# 05_LMS7002M_RF.net
KiCad netlist of a schematic drawn in Altium Designer
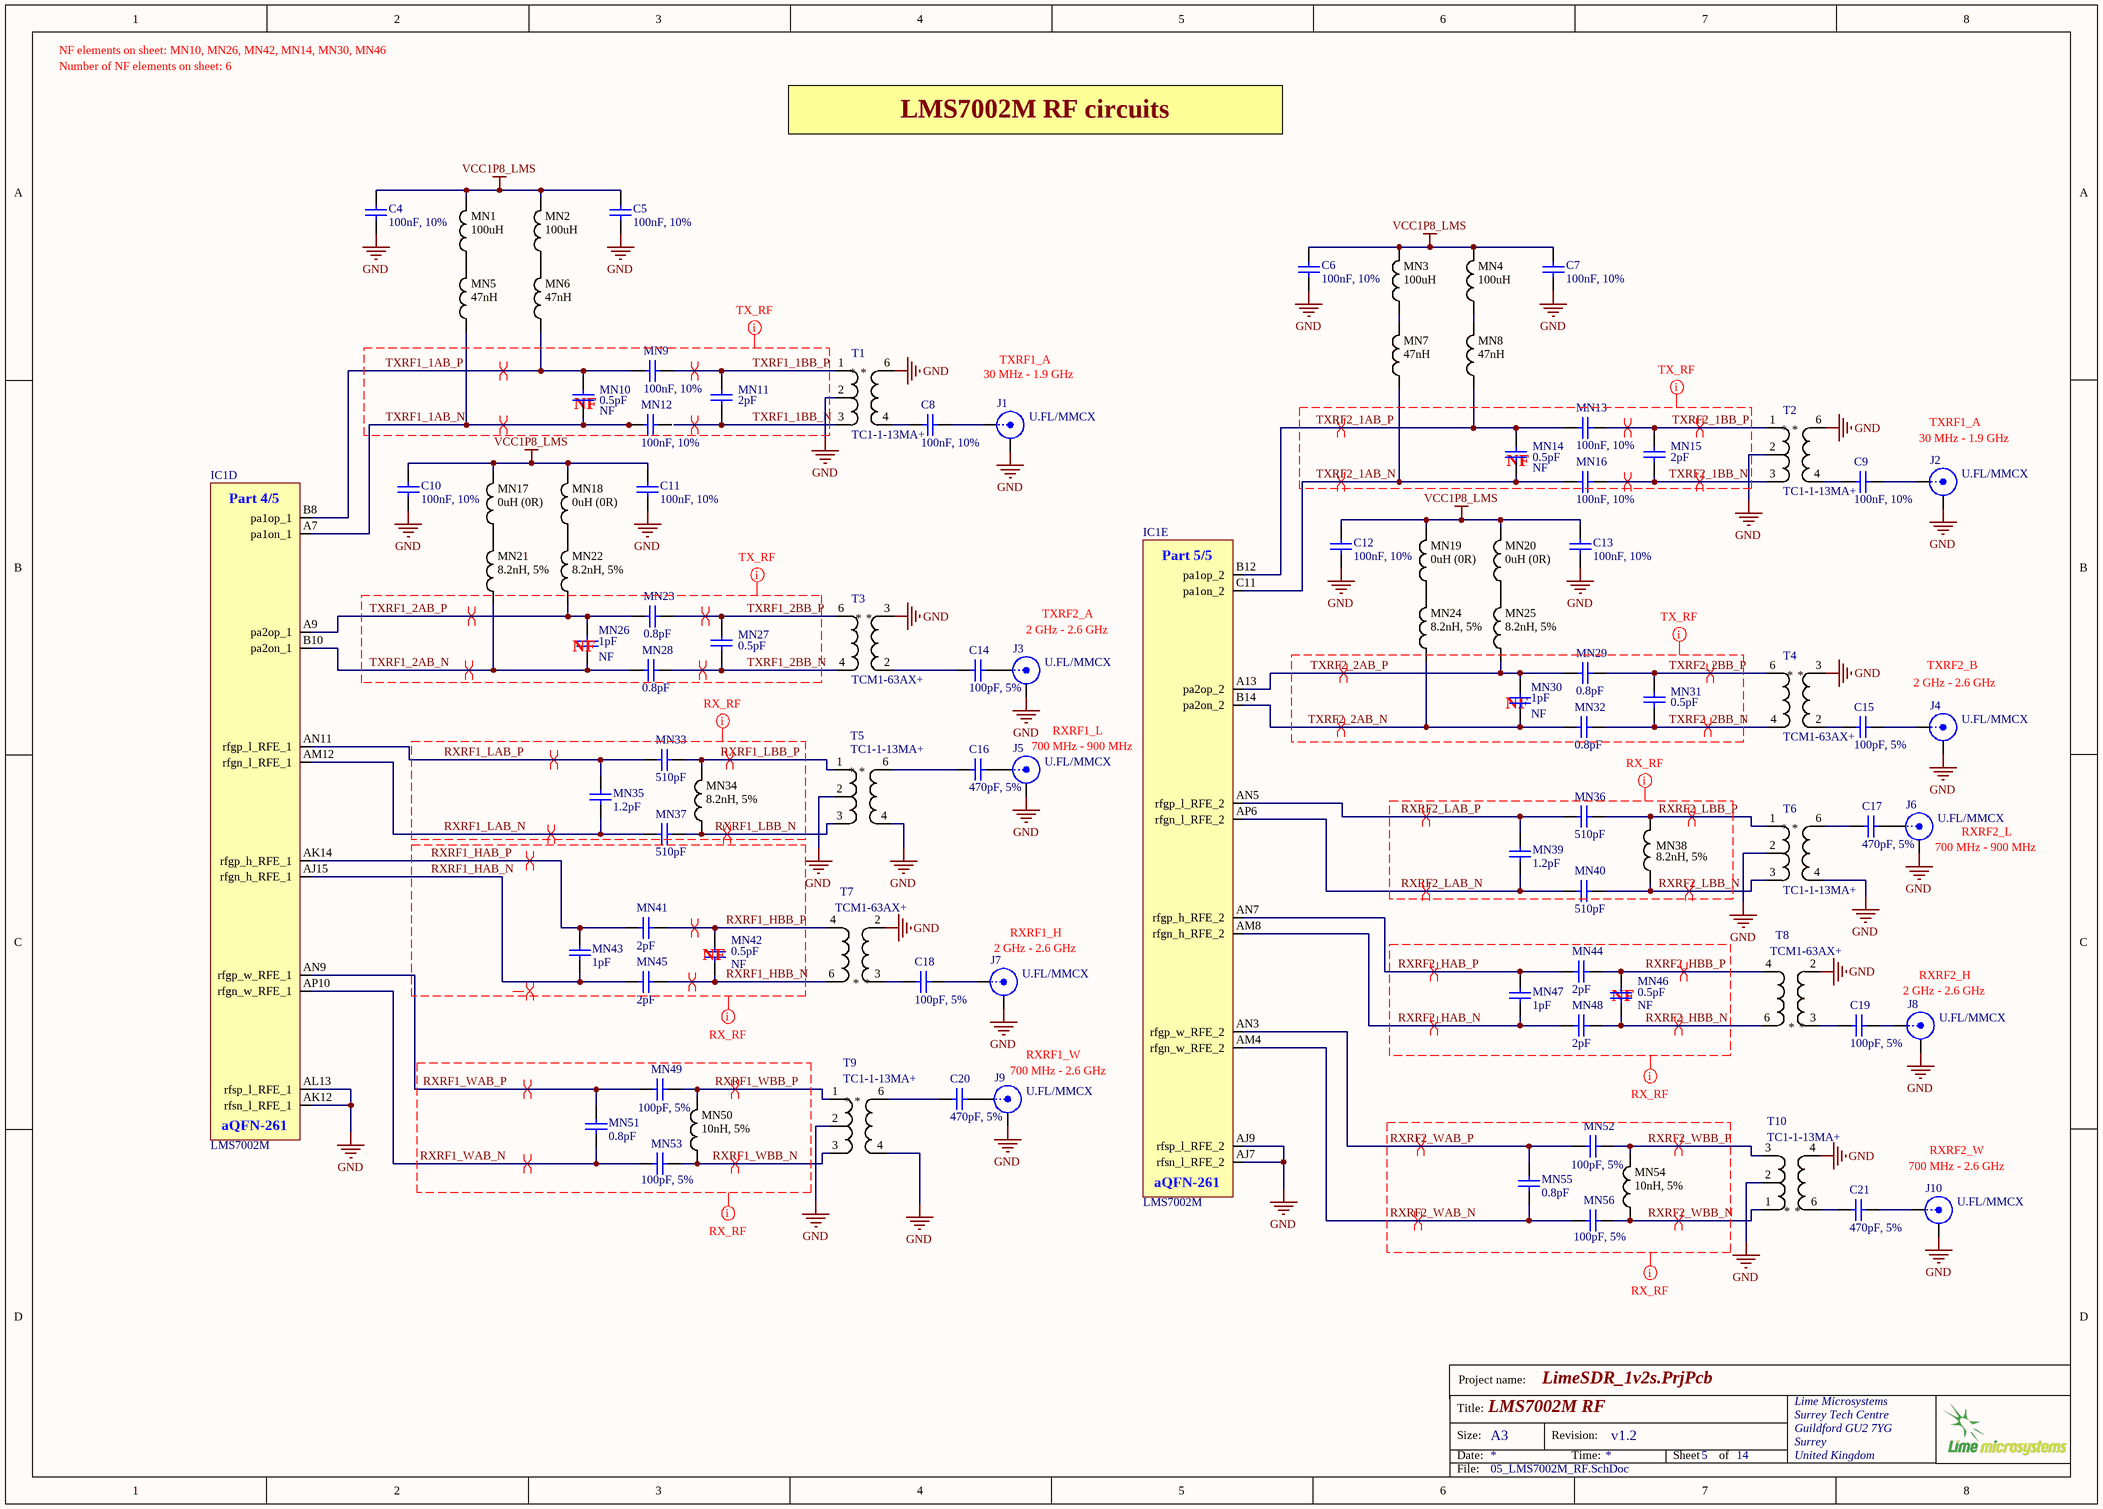
[diagram p0: 05_LMS7002M_RF.SchDoc]

(export (version "E")
  (design (tool "Eeschema 10.0.6"))
  (components
    (comp (ref "C4")
      (value "100nF, 10%")
      (footprint "CAP0402")
      (fields
        (field (name "MANUFACTURER") "Murata Electronics")
        (field (name "TOLERANCE") "10 %")
        (field (name "MANUFACTURER PART NUMBER") "GRM155R71C104KA88D")
      )
      (libsource (lib "LimeMicroAltiumLib_schLib") (part "Cap_0402"))
    )
    (comp (ref "C5")
      (value "100nF, 10%")
      (footprint "CAP0402")
      (fields
        (field (name "MANUFACTURER") "Murata Electronics")
        (field (name "TOLERANCE") "10 %")
        (field (name "MANUFACTURER PART NUMBER") "GRM155R71C104KA88D")
      )
      (libsource (lib "LimeMicroAltiumLib_schLib") (part "Cap_0402"))
    )
    (comp (ref "C6")
      (value "100nF, 10%")
      (footprint "CAP0402")
      (fields
        (field (name "MANUFACTURER") "Murata Electronics")
        (field (name "TOLERANCE") "10 %")
        (field (name "MANUFACTURER PART NUMBER") "GRM155R71C104KA88D")
      )
      (libsource (lib "LimeMicroAltiumLib_schLib") (part "Cap_0402"))
    )
    (comp (ref "C7")
      (value "100nF, 10%")
      (footprint "CAP0402")
      (fields
        (field (name "MANUFACTURER") "Murata Electronics")
        (field (name "TOLERANCE") "10 %")
        (field (name "MANUFACTURER PART NUMBER") "GRM155R71C104KA88D")
      )
      (libsource (lib "LimeMicroAltiumLib_schLib") (part "Cap_0402"))
    )
    (comp (ref "C8")
      (value "100nF, 10%")
      (footprint "CAP0402")
      (fields
        (field (name "MANUFACTURER") "Murata Electronics")
        (field (name "TOLERANCE") "10 %")
        (field (name "MANUFACTURER PART NUMBER") "GRM155R71C104KA88D")
      )
      (libsource (lib "LimeMicroAltiumLib_schLib") (part "Cap_0402"))
    )
    (comp (ref "C9")
      (value "100nF, 10%")
      (footprint "CAP0402")
      (fields
        (field (name "MANUFACTURER") "Murata Electronics")
        (field (name "TOLERANCE") "10 %")
        (field (name "MANUFACTURER PART NUMBER") "GRM155R71C104KA88D")
      )
      (libsource (lib "LimeMicroAltiumLib_schLib") (part "Cap_0402"))
    )
    (comp (ref "C10")
      (value "100nF, 10%")
      (footprint "CAP0402")
      (fields
        (field (name "MANUFACTURER") "Murata Electronics")
        (field (name "TOLERANCE") "10 %")
        (field (name "MANUFACTURER PART NUMBER") "GRM155R71C104KA88D")
      )
      (libsource (lib "LimeMicroAltiumLib_schLib") (part "Cap_0402"))
    )
    (comp (ref "C11")
      (value "100nF, 10%")
      (footprint "CAP0402")
      (fields
        (field (name "MANUFACTURER") "Murata Electronics")
        (field (name "TOLERANCE") "10 %")
        (field (name "MANUFACTURER PART NUMBER") "GRM155R71C104KA88D")
      )
      (libsource (lib "LimeMicroAltiumLib_schLib") (part "Cap_0402"))
    )
    (comp (ref "C12")
      (value "100nF, 10%")
      (footprint "CAP0402")
      (fields
        (field (name "MANUFACTURER") "Murata Electronics")
        (field (name "TOLERANCE") "10 %")
        (field (name "MANUFACTURER PART NUMBER") "GRM155R71C104KA88D")
      )
      (libsource (lib "LimeMicroAltiumLib_schLib") (part "Cap_0402"))
    )
    (comp (ref "C13")
      (value "100nF, 10%")
      (footprint "CAP0402")
      (fields
        (field (name "MANUFACTURER") "Murata Electronics")
        (field (name "TOLERANCE") "10 %")
        (field (name "MANUFACTURER PART NUMBER") "GRM155R71C104KA88D")
      )
      (libsource (lib "LimeMicroAltiumLib_schLib") (part "Cap_0402"))
    )
    (comp (ref "C14")
      (value "100pF, 5%")
      (footprint "CAP0402")
      (fields (field (name "TOLERANCE") "±5%") (field (name "MANUFACTURER") "Yageo"))
      (libsource (lib "LimeMicroAltiumLib_schLib") (part "Cap_0402"))
    )
    (comp (ref "C15")
      (value "100pF, 5%")
      (footprint "CAP0402")
      (fields (field (name "TOLERANCE") "±5%") (field (name "MANUFACTURER") "Yageo"))
      (libsource (lib "LimeMicroAltiumLib_schLib") (part "Cap_0402"))
    )
    (comp (ref "C16")
      (value "470pF, 5%")
      (footprint "CAP0402")
      (fields
        (field (name "MANUFACTURER PART NUMBER") "C1005C0G1H471J050BA")
        (field (name "TOLERANCE") "±5%")
        (field (name "MANUFACTURER") "TDK Corporation")
      )
      (libsource (lib "LimeMicroAltiumLib_schLib") (part "Cap_0402"))
    )
    (comp (ref "C17")
      (value "470pF, 5%")
      (footprint "CAP0402")
      (fields
        (field (name "MANUFACTURER PART NUMBER") "C1005C0G1H471J050BA")
        (field (name "TOLERANCE") "±5%")
        (field (name "MANUFACTURER") "TDK Corporation")
      )
      (libsource (lib "LimeMicroAltiumLib_schLib") (part "Cap_0402"))
    )
    (comp (ref "C18")
      (value "100pF, 5%")
      (footprint "CAP0402")
      (fields (field (name "TOLERANCE") "±5%") (field (name "MANUFACTURER") "Yageo"))
      (libsource (lib "LimeMicroAltiumLib_schLib") (part "Cap_0402"))
    )
    (comp (ref "C19")
      (value "100pF, 5%")
      (footprint "CAP0402")
      (fields (field (name "TOLERANCE") "±5%") (field (name "MANUFACTURER") "Yageo"))
      (libsource (lib "LimeMicroAltiumLib_schLib") (part "Cap_0402"))
    )
    (comp (ref "C20")
      (value "470pF, 5%")
      (footprint "CAP0402")
      (fields
        (field (name "MANUFACTURER PART NUMBER") "C1005C0G1H471J050BA")
        (field (name "TOLERANCE") "±5%")
        (field (name "MANUFACTURER") "TDK Corporation")
      )
      (libsource (lib "LimeMicroAltiumLib_schLib") (part "Cap_0402"))
    )
    (comp (ref "C21")
      (value "470pF, 5%")
      (footprint "CAP0402")
      (fields
        (field (name "MANUFACTURER PART NUMBER") "C1005C0G1H471J050BA")
        (field (name "TOLERANCE") "±5%")
        (field (name "MANUFACTURER") "TDK Corporation")
      )
      (libsource (lib "LimeMicroAltiumLib_schLib") (part "Cap_0402"))
    )
    (comp (ref "IC1")
      (value "LMS7002M")
      (footprint "LMS7002M")
      (fields (field (name "MANUFACTURER") "Lime Microsystems"))
      (libsource (lib "LimeMicroAltiumLib_schLib") (part "LMS7002M"))
    )
    (comp (ref "J1")
      (value "U.FL/MMCX")
      (footprint "MMCX_UFL_conn_u")
      (description "CONN UMC RCPT STR 50 OHM SMD")
      (fields (field (name "MANUFACTURER") "Molex, LLC"))
      (libsource (lib "LimeMicroAltiumLib_schLib") (part "RF_IF_connector"))
    )
    (comp (ref "J2")
      (value "U.FL/MMCX")
      (footprint "MMCX_UFL_conn_u")
      (description "CONN UMC RCPT STR 50 OHM SMD")
      (fields (field (name "MANUFACTURER") "Molex, LLC"))
      (libsource (lib "LimeMicroAltiumLib_schLib") (part "RF_IF_connector"))
    )
    (comp (ref "J3")
      (value "U.FL/MMCX")
      (footprint "MMCX_UFL_conn_u")
      (description "CONN UMC RCPT STR 50 OHM SMD")
      (fields (field (name "MANUFACTURER") "Molex, LLC"))
      (libsource (lib "LimeMicroAltiumLib_schLib") (part "RF_IF_connector"))
    )
    (comp (ref "J4")
      (value "U.FL/MMCX")
      (footprint "MMCX_UFL_conn_u")
      (description "CONN UMC RCPT STR 50 OHM SMD")
      (fields (field (name "MANUFACTURER") "Molex, LLC"))
      (libsource (lib "LimeMicroAltiumLib_schLib") (part "RF_IF_connector"))
    )
    (comp (ref "J5")
      (value "U.FL/MMCX")
      (footprint "MMCX_UFL_conn_u")
      (description "CONN UMC RCPT STR 50 OHM SMD")
      (fields (field (name "MANUFACTURER") "Molex, LLC"))
      (libsource (lib "LimeMicroAltiumLib_schLib") (part "RF_IF_connector"))
    )
    (comp (ref "J6")
      (value "U.FL/MMCX")
      (footprint "MMCX_UFL_conn_u")
      (description "CONN UMC RCPT STR 50 OHM SMD")
      (fields (field (name "MANUFACTURER") "Molex, LLC"))
      (libsource (lib "LimeMicroAltiumLib_schLib") (part "RF_IF_connector"))
    )
    (comp (ref "J7")
      (value "U.FL/MMCX")
      (footprint "MMCX_UFL_conn_u")
      (description "CONN UMC RCPT STR 50 OHM SMD")
      (fields (field (name "MANUFACTURER") "Molex, LLC"))
      (libsource (lib "LimeMicroAltiumLib_schLib") (part "RF_IF_connector"))
    )
    (comp (ref "J8")
      (value "U.FL/MMCX")
      (footprint "MMCX_UFL_conn_u")
      (description "CONN UMC RCPT STR 50 OHM SMD")
      (fields (field (name "MANUFACTURER") "Molex, LLC"))
      (libsource (lib "LimeMicroAltiumLib_schLib") (part "RF_IF_connector"))
    )
    (comp (ref "J9")
      (value "U.FL/MMCX")
      (footprint "MMCX_UFL_conn_u")
      (description "CONN UMC RCPT STR 50 OHM SMD")
      (fields (field (name "MANUFACTURER") "Molex, LLC"))
      (libsource (lib "LimeMicroAltiumLib_schLib") (part "RF_IF_connector"))
    )
    (comp (ref "J10")
      (value "U.FL/MMCX")
      (footprint "MMCX_UFL_conn_u")
      (description "CONN UMC RCPT STR 50 OHM SMD")
      (fields (field (name "MANUFACTURER") "Molex, LLC"))
      (libsource (lib "LimeMicroAltiumLib_schLib") (part "RF_IF_connector"))
    )
    (comp (ref "MN1")
      (value "100uH")
      (footprint "RES0805")
      (fields
        (field (name "TOLERANCE") "±10%")
        (field (name "MANUFACTURER") "TDK Corporation")
        (field (name "MANUFACTURER PART NUMBER") "MLF2012C101KT000")
      )
      (libsource (lib "LimeMicroAltiumLib_schLib") (part "Inductor_0603"))
    )
    (comp (ref "MN2")
      (value "100uH")
      (footprint "RES0805")
      (fields
        (field (name "TOLERANCE") "±10%")
        (field (name "MANUFACTURER") "TDK Corporation")
        (field (name "MANUFACTURER PART NUMBER") "MLF2012C101KT000")
      )
      (libsource (lib "LimeMicroAltiumLib_schLib") (part "Inductor_0603"))
    )
    (comp (ref "MN3")
      (value "100uH")
      (footprint "RES0805")
      (fields
        (field (name "TOLERANCE") "±10%")
        (field (name "MANUFACTURER") "TDK Corporation")
        (field (name "MANUFACTURER PART NUMBER") "MLF2012C101KT000")
      )
      (libsource (lib "LimeMicroAltiumLib_schLib") (part "Inductor_0603"))
    )
    (comp (ref "MN4")
      (value "100uH")
      (footprint "RES0805")
      (fields
        (field (name "TOLERANCE") "±10%")
        (field (name "MANUFACTURER") "TDK Corporation")
        (field (name "MANUFACTURER PART NUMBER") "MLF2012C101KT000")
      )
      (libsource (lib "LimeMicroAltiumLib_schLib") (part "Inductor_0603"))
    )
    (comp (ref "MN5")
      (value "47nH")
      (footprint "RES0402")
      (fields
        (field (name "MANUFACTURER") "COILCRAFT")
        (field (name "MANUFACTURER PART NUMBER") "0402HP-47NXJLU")
      )
      (libsource (lib "LimeMicroAltiumLib_schLib") (part "Inductor_0603"))
    )
    (comp (ref "MN6")
      (value "47nH")
      (footprint "RES0402")
      (fields
        (field (name "MANUFACTURER") "COILCRAFT")
        (field (name "MANUFACTURER PART NUMBER") "0402HP-47NXJLU")
      )
      (libsource (lib "LimeMicroAltiumLib_schLib") (part "Inductor_0603"))
    )
    (comp (ref "MN7")
      (value "47nH")
      (footprint "RES0402")
      (fields
        (field (name "MANUFACTURER") "COILCRAFT")
        (field (name "MANUFACTURER PART NUMBER") "0402HP-47NXJLU")
      )
      (libsource (lib "LimeMicroAltiumLib_schLib") (part "Inductor_0603"))
    )
    (comp (ref "MN8")
      (value "47nH")
      (footprint "RES0402")
      (fields
        (field (name "MANUFACTURER") "COILCRAFT")
        (field (name "MANUFACTURER PART NUMBER") "0402HP-47NXJLU")
      )
      (libsource (lib "LimeMicroAltiumLib_schLib") (part "Inductor_0603"))
    )
    (comp (ref "MN9")
      (value "100nF, 10%")
      (footprint "CAP0402")
      (fields
        (field (name "MANUFACTURER") "Murata Electronics")
        (field (name "TOLERANCE") "10 %")
        (field (name "MANUFACTURER PART NUMBER") "GRM155R71C104KA88D")
      )
      (libsource (lib "LimeMicroAltiumLib_schLib") (part "Cap_0402"))
    )
    (comp (ref "MN10")
      (value "0.5pF")
      (footprint "CAP0402")
      (fields
        (field (name "ASSEMBLY INFO") "NF")
        (field (name "TOLERANCE") "±0.25pF")
        (field (name "MANUFACTURER") "Yageo")
      )
      (libsource (lib "LimeMicroAltiumLib_schLib") (part "Cap_0402"))
    )
    (comp (ref "MN11")
      (value "2pF")
      (footprint "CAP0402")
      (fields (field (name "MANUFACTURER PART NUMBER") "04025U2R0BAT2A") (field (name "MANUFACTURER") "AVX"))
      (libsource (lib "LimeMicroAltiumLib_schLib") (part "Cap_0402"))
    )
    (comp (ref "MN12")
      (value "100nF, 10%")
      (footprint "CAP0402")
      (fields
        (field (name "MANUFACTURER") "Murata Electronics")
        (field (name "TOLERANCE") "10 %")
        (field (name "MANUFACTURER PART NUMBER") "GRM155R71C104KA88D")
      )
      (libsource (lib "LimeMicroAltiumLib_schLib") (part "Cap_0402"))
    )
    (comp (ref "MN13")
      (value "100nF, 10%")
      (footprint "CAP0402")
      (fields
        (field (name "MANUFACTURER") "Murata Electronics")
        (field (name "TOLERANCE") "10 %")
        (field (name "MANUFACTURER PART NUMBER") "GRM155R71C104KA88D")
      )
      (libsource (lib "LimeMicroAltiumLib_schLib") (part "Cap_0402"))
    )
    (comp (ref "MN14")
      (value "0.5pF")
      (footprint "CAP0402")
      (fields
        (field (name "ASSEMBLY INFO") "NF")
        (field (name "TOLERANCE") "±0.25pF")
        (field (name "MANUFACTURER") "Yageo")
      )
      (libsource (lib "LimeMicroAltiumLib_schLib") (part "Cap_0402"))
    )
    (comp (ref "MN15")
      (value "2pF")
      (footprint "CAP0402")
      (fields (field (name "MANUFACTURER PART NUMBER") "04025U2R0BAT2A") (field (name "MANUFACTURER") "AVX"))
      (libsource (lib "LimeMicroAltiumLib_schLib") (part "Cap_0402"))
    )
    (comp (ref "MN16")
      (value "100nF, 10%")
      (footprint "CAP0402")
      (fields
        (field (name "MANUFACTURER") "Murata Electronics")
        (field (name "TOLERANCE") "10 %")
        (field (name "MANUFACTURER PART NUMBER") "GRM155R71C104KA88D")
      )
      (libsource (lib "LimeMicroAltiumLib_schLib") (part "Cap_0402"))
    )
    (comp (ref "MN17")
      (value "0uH (0R)")
      (footprint "RES0805")
      (fields (field (name "MANUFACTURER") "BOURNS"))
      (libsource (lib "LimeMicroAltiumLib_schLib") (part "Inductor_0603"))
    )
    (comp (ref "MN18")
      (value "0uH (0R)")
      (footprint "RES0805")
      (fields (field (name "MANUFACTURER") "BOURNS"))
      (libsource (lib "LimeMicroAltiumLib_schLib") (part "Inductor_0603"))
    )
    (comp (ref "MN19")
      (value "0uH (0R)")
      (footprint "RES0805")
      (fields (field (name "MANUFACTURER") "BOURNS"))
      (libsource (lib "LimeMicroAltiumLib_schLib") (part "Inductor_0603"))
    )
    (comp (ref "MN20")
      (value "0uH (0R)")
      (footprint "RES0805")
      (fields (field (name "MANUFACTURER") "BOURNS"))
      (libsource (lib "LimeMicroAltiumLib_schLib") (part "Inductor_0603"))
    )
    (comp (ref "MN21")
      (value "8.2nH, 5%")
      (footprint "RES0402")
      (fields (field (name "MANUFACTURER") "COILCRAFT"))
      (libsource (lib "LimeMicroAltiumLib_schLib") (part "Inductor_0603"))
    )
    (comp (ref "MN22")
      (value "8.2nH, 5%")
      (footprint "RES0402")
      (fields (field (name "MANUFACTURER") "COILCRAFT"))
      (libsource (lib "LimeMicroAltiumLib_schLib") (part "Inductor_0603"))
    )
    (comp (ref "MN23")
      (value "0.8pF")
      (footprint "CAP0402")
      (fields
        (field (name "TOLERANCE") "±0.1pF")
        (field (name "MANUFACTURER") "Murata Electronics North America")
        (field (name "MANUFACTURER PART NUMBER") "GRM1555C1HR80BA01D")
      )
      (libsource (lib "LimeMicroAltiumLib_schLib") (part "Cap_0402"))
    )
    (comp (ref "MN24")
      (value "8.2nH, 5%")
      (footprint "RES0402")
      (fields (field (name "MANUFACTURER") "COILCRAFT"))
      (libsource (lib "LimeMicroAltiumLib_schLib") (part "Inductor_0603"))
    )
    (comp (ref "MN25")
      (value "8.2nH, 5%")
      (footprint "RES0402")
      (fields (field (name "MANUFACTURER") "COILCRAFT"))
      (libsource (lib "LimeMicroAltiumLib_schLib") (part "Inductor_0603"))
    )
    (comp (ref "MN26")
      (value "1pF")
      (footprint "CAP0402")
      (fields
        (field (name "ASSEMBLY INFO") "NF")
        (field (name "MANUFACTURER") "TDK Corporation")
        (field (name "TOLERANCE") "±0.1pF")
      )
      (libsource (lib "LimeMicroAltiumLib_schLib") (part "Cap_0402"))
    )
    (comp (ref "MN27")
      (value "0.5pF")
      (footprint "CAP0402")
      (fields (field (name "TOLERANCE") "±0.25pF") (field (name "MANUFACTURER") "Yageo"))
      (libsource (lib "LimeMicroAltiumLib_schLib") (part "Cap_0402"))
    )
    (comp (ref "MN28")
      (value "0.8pF")
      (footprint "CAP0402")
      (fields
        (field (name "TOLERANCE") "±0.1pF")
        (field (name "MANUFACTURER") "Murata Electronics North America")
        (field (name "MANUFACTURER PART NUMBER") "GRM1555C1HR80BA01D")
      )
      (libsource (lib "LimeMicroAltiumLib_schLib") (part "Cap_0402"))
    )
    (comp (ref "MN29")
      (value "0.8pF")
      (footprint "CAP0402")
      (fields
        (field (name "TOLERANCE") "±0.1pF")
        (field (name "MANUFACTURER") "Murata Electronics North America")
        (field (name "MANUFACTURER PART NUMBER") "GRM1555C1HR80BA01D")
      )
      (libsource (lib "LimeMicroAltiumLib_schLib") (part "Cap_0402"))
    )
    (comp (ref "MN30")
      (value "1pF")
      (footprint "CAP0402")
      (fields
        (field (name "ASSEMBLY INFO") "NF")
        (field (name "MANUFACTURER") "TDK Corporation")
        (field (name "TOLERANCE") "±0.1pF")
      )
      (libsource (lib "LimeMicroAltiumLib_schLib") (part "Cap_0402"))
    )
    (comp (ref "MN31")
      (value "0.5pF")
      (footprint "CAP0402")
      (fields (field (name "TOLERANCE") "±0.25pF") (field (name "MANUFACTURER") "Yageo"))
      (libsource (lib "LimeMicroAltiumLib_schLib") (part "Cap_0402"))
    )
    (comp (ref "MN32")
      (value "0.8pF")
      (footprint "CAP0402")
      (fields
        (field (name "TOLERANCE") "±0.1pF")
        (field (name "MANUFACTURER") "Murata Electronics North America")
        (field (name "MANUFACTURER PART NUMBER") "GRM1555C1HR80BA01D")
      )
      (libsource (lib "LimeMicroAltiumLib_schLib") (part "Cap_0402"))
    )
    (comp (ref "MN33")
      (value "510pF")
      (footprint "CAP0402")
      (fields
        (field (name "TOLERANCE") "±5%")
        (field (name "MANUFACTURER") "Murata Electronics North America")
        (field (name "MANUFACTURER PART NUMBER") "GRM1555C1H511JA01D")
      )
      (libsource (lib "LimeMicroAltiumLib_schLib") (part "Cap_0402"))
    )
    (comp (ref "MN34")
      (value "8.2nH, 5%")
      (footprint "RES0402")
      (fields (field (name "MANUFACTURER") "COILCRAFT"))
      (libsource (lib "LimeMicroAltiumLib_schLib") (part "Inductor_0603"))
    )
    (comp (ref "MN35")
      (value "1.2pF")
      (footprint "CAP0402")
      (fields
        (field (name "MANUFACTURER") "Murata Electronics North America")
        (field (name "MANUFACTURER PART NUMBER") "GRM1555C1H1R2CA01D")
        (field (name "TOLERANCE") "±0.25pF")
      )
      (libsource (lib "LimeMicroAltiumLib_schLib") (part "Cap_0402"))
    )
    (comp (ref "MN36")
      (value "510pF")
      (footprint "CAP0402")
      (fields
        (field (name "TOLERANCE") "±5%")
        (field (name "MANUFACTURER") "Murata Electronics North America")
        (field (name "MANUFACTURER PART NUMBER") "GRM1555C1H511JA01D")
      )
      (libsource (lib "LimeMicroAltiumLib_schLib") (part "Cap_0402"))
    )
    (comp (ref "MN37")
      (value "510pF")
      (footprint "CAP0402")
      (fields
        (field (name "TOLERANCE") "±5%")
        (field (name "MANUFACTURER") "Murata Electronics North America")
        (field (name "MANUFACTURER PART NUMBER") "GRM1555C1H511JA01D")
      )
      (libsource (lib "LimeMicroAltiumLib_schLib") (part "Cap_0402"))
    )
    (comp (ref "MN38")
      (value "8.2nH, 5%")
      (footprint "RES0402")
      (fields (field (name "MANUFACTURER") "COILCRAFT"))
      (libsource (lib "LimeMicroAltiumLib_schLib") (part "Inductor_0603"))
    )
    (comp (ref "MN39")
      (value "1.2pF")
      (footprint "CAP0402")
      (fields
        (field (name "MANUFACTURER") "Murata Electronics North America")
        (field (name "MANUFACTURER PART NUMBER") "GRM1555C1H1R2CA01D")
        (field (name "TOLERANCE") "±0.25pF")
      )
      (libsource (lib "LimeMicroAltiumLib_schLib") (part "Cap_0402"))
    )
    (comp (ref "MN40")
      (value "510pF")
      (footprint "CAP0402")
      (fields
        (field (name "TOLERANCE") "±5%")
        (field (name "MANUFACTURER") "Murata Electronics North America")
        (field (name "MANUFACTURER PART NUMBER") "GRM1555C1H511JA01D")
      )
      (libsource (lib "LimeMicroAltiumLib_schLib") (part "Cap_0402"))
    )
    (comp (ref "MN41")
      (value "2pF")
      (footprint "CAP0402")
      (fields (field (name "MANUFACTURER PART NUMBER") "04025U2R0BAT2A") (field (name "MANUFACTURER") "AVX"))
      (libsource (lib "LimeMicroAltiumLib_schLib") (part "Cap_0402"))
    )
    (comp (ref "MN42")
      (value "0.5pF")
      (footprint "CAP0402")
      (fields
        (field (name "ASSEMBLY INFO") "NF")
        (field (name "TOLERANCE") "±0.25pF")
        (field (name "MANUFACTURER") "Yageo")
      )
      (libsource (lib "LimeMicroAltiumLib_schLib") (part "Cap_0402"))
    )
    (comp (ref "MN43")
      (value "1pF")
      (footprint "CAP0402")
      (fields (field (name "MANUFACTURER") "TDK Corporation") (field (name "TOLERANCE") "±0.1pF"))
      (libsource (lib "LimeMicroAltiumLib_schLib") (part "Cap_0402"))
    )
    (comp (ref "MN44")
      (value "2pF")
      (footprint "CAP0402")
      (fields (field (name "MANUFACTURER PART NUMBER") "04025U2R0BAT2A") (field (name "MANUFACTURER") "AVX"))
      (libsource (lib "LimeMicroAltiumLib_schLib") (part "Cap_0402"))
    )
    (comp (ref "MN45")
      (value "2pF")
      (footprint "CAP0402")
      (fields (field (name "MANUFACTURER PART NUMBER") "04025U2R0BAT2A") (field (name "MANUFACTURER") "AVX"))
      (libsource (lib "LimeMicroAltiumLib_schLib") (part "Cap_0402"))
    )
    (comp (ref "MN46")
      (value "0.5pF")
      (footprint "CAP0402")
      (fields
        (field (name "ASSEMBLY INFO") "NF")
        (field (name "TOLERANCE") "±0.25pF")
        (field (name "MANUFACTURER") "Yageo")
      )
      (libsource (lib "LimeMicroAltiumLib_schLib") (part "Cap_0402"))
    )
    (comp (ref "MN47")
      (value "1pF")
      (footprint "CAP0402")
      (fields (field (name "MANUFACTURER") "TDK Corporation") (field (name "TOLERANCE") "±0.1pF"))
      (libsource (lib "LimeMicroAltiumLib_schLib") (part "Cap_0402"))
    )
    (comp (ref "MN48")
      (value "2pF")
      (footprint "CAP0402")
      (fields (field (name "MANUFACTURER PART NUMBER") "04025U2R0BAT2A") (field (name "MANUFACTURER") "AVX"))
      (libsource (lib "LimeMicroAltiumLib_schLib") (part "Cap_0402"))
    )
    (comp (ref "MN49")
      (value "100pF, 5%")
      (footprint "CAP0402")
      (fields (field (name "TOLERANCE") "±5%") (field (name "MANUFACTURER") "Yageo"))
      (libsource (lib "LimeMicroAltiumLib_schLib") (part "Cap_0402"))
    )
    (comp (ref "MN50")
      (value "10nH, 5%")
      (footprint "RES0402")
      (fields (field (name "MANUFACTURER") "COILCRAFT"))
      (libsource (lib "LimeMicroAltiumLib_schLib") (part "Inductor_0603"))
    )
    (comp (ref "MN51")
      (value "0.8pF")
      (footprint "CAP0402")
      (fields
        (field (name "TOLERANCE") "±0.1pF")
        (field (name "MANUFACTURER") "Murata Electronics North America")
        (field (name "MANUFACTURER PART NUMBER") "GRM1555C1HR80BA01D")
      )
      (libsource (lib "LimeMicroAltiumLib_schLib") (part "Cap_0402"))
    )
    (comp (ref "MN52")
      (value "100pF, 5%")
      (footprint "CAP0402")
      (fields (field (name "TOLERANCE") "±5%") (field (name "MANUFACTURER") "Yageo"))
      (libsource (lib "LimeMicroAltiumLib_schLib") (part "Cap_0402"))
    )
    (comp (ref "MN53")
      (value "100pF, 5%")
      (footprint "CAP0402")
      (fields (field (name "TOLERANCE") "±5%") (field (name "MANUFACTURER") "Yageo"))
      (libsource (lib "LimeMicroAltiumLib_schLib") (part "Cap_0402"))
    )
    (comp (ref "MN54")
      (value "10nH, 5%")
      (footprint "RES0402")
      (fields (field (name "MANUFACTURER") "COILCRAFT"))
      (libsource (lib "LimeMicroAltiumLib_schLib") (part "Inductor_0603"))
    )
    (comp (ref "MN55")
      (value "0.8pF")
      (footprint "CAP0402")
      (fields
        (field (name "TOLERANCE") "±0.1pF")
        (field (name "MANUFACTURER") "Murata Electronics North America")
        (field (name "MANUFACTURER PART NUMBER") "GRM1555C1HR80BA01D")
      )
      (libsource (lib "LimeMicroAltiumLib_schLib") (part "Cap_0402"))
    )
    (comp (ref "MN56")
      (value "100pF, 5%")
      (footprint "CAP0402")
      (fields (field (name "TOLERANCE") "±5%") (field (name "MANUFACTURER") "Yageo"))
      (libsource (lib "LimeMicroAltiumLib_schLib") (part "Cap_0402"))
    )
    (comp (ref "T1")
      (value "TC1-1-13MA+")
      (footprint "TC1-1-13MA+_v2")
      (fields (field (name "MANUFACTURER") "Mini-Circuits"))
      (libsource (lib "LimeMicroAltiumLib_schLib") (part "Balun"))
    )
    (comp (ref "T2")
      (value "TC1-1-13MA+")
      (footprint "TC1-1-13MA+_v2")
      (fields (field (name "MANUFACTURER") "Mini-Circuits"))
      (libsource (lib "LimeMicroAltiumLib_schLib") (part "Balun"))
    )
    (comp (ref "T3")
      (value "TCM1-63AX+")
      (footprint "TCM1-63AX+_v2")
      (fields (field (name "MANUFACTURER") "Mini-circuits"))
      (libsource (lib "LimeMicroAltiumLib_schLib") (part "Balun_v2"))
    )
    (comp (ref "T4")
      (value "TCM1-63AX+")
      (footprint "TCM1-63AX+_v2")
      (fields (field (name "MANUFACTURER") "Mini-circuits"))
      (libsource (lib "LimeMicroAltiumLib_schLib") (part "Balun_v2"))
    )
    (comp (ref "T5")
      (value "TC1-1-13MA+")
      (footprint "TC1-1-13MA+_v2")
      (fields (field (name "MANUFACTURER") "Mini-Circuits"))
      (libsource (lib "LimeMicroAltiumLib_schLib") (part "Balun"))
    )
    (comp (ref "T6")
      (value "TC1-1-13MA+")
      (footprint "TC1-1-13MA+_v2")
      (fields (field (name "MANUFACTURER") "Mini-Circuits"))
      (libsource (lib "LimeMicroAltiumLib_schLib") (part "Balun"))
    )
    (comp (ref "T7")
      (value "TCM1-63AX+")
      (footprint "TCM1-63AX+_v2")
      (fields (field (name "MANUFACTURER") "Mini-circuits"))
      (libsource (lib "") (part "Balun_v2_1"))
    )
    (comp (ref "T8")
      (value "TCM1-63AX+")
      (footprint "TCM1-63AX+_v2")
      (fields (field (name "MANUFACTURER") "Mini-circuits"))
      (libsource (lib "") (part "Balun_v2_1"))
    )
    (comp (ref "T9")
      (value "TC1-1-13MA+")
      (footprint "TC1-1-13MA+_v2")
      (fields (field (name "MANUFACTURER") "Mini-Circuits"))
      (libsource (lib "LimeMicroAltiumLib_schLib") (part "Balun"))
    )
    (comp (ref "T10")
      (value "TC1-1-13MA+")
      (footprint "TC1-1-13MA+_v2")
      (fields (field (name "MANUFACTURER") "Mini-Circuits"))
      (libsource (lib "") (part "Balun_1"))
    )
  )
  (nets
    (net (code "1") (name "/RXRF1_HAB_N") (class "Default")
      (node (ref "IC1") (pin "AJ15") (pinfunction "rfgn_h_RFE_1_AJ15") (pintype "passive"))
      (node (ref "MN43") (pin "1") (pinfunction "1_1") (pintype "passive"))
      (node (ref "MN45") (pin "2") (pinfunction "2_2") (pintype "passive"))
    )
    (net (code "2") (name "/RXRF1_HAB_P") (class "Default")
      (node (ref "IC1") (pin "AK14") (pinfunction "rfgp_h_RFE_1_AK14") (pintype "passive"))
      (node (ref "MN41") (pin "2") (pinfunction "2_2") (pintype "passive"))
      (node (ref "MN43") (pin "2") (pinfunction "2_2") (pintype "passive"))
    )
    (net (code "3") (name "/RXRF1_HBB_N") (class "Default")
      (node (ref "MN42") (pin "1") (pinfunction "1_1") (pintype "passive"))
      (node (ref "MN45") (pin "1") (pinfunction "1_1") (pintype "passive"))
      (node (ref "T7") (pin "6") (pinfunction "6_6") (pintype "passive"))
    )
    (net (code "4") (name "/RXRF1_HBB_P") (class "Default")
      (node (ref "MN41") (pin "1") (pinfunction "1_1") (pintype "passive"))
      (node (ref "MN42") (pin "2") (pinfunction "2_2") (pintype "passive"))
      (node (ref "T7") (pin "4") (pinfunction "4_4") (pintype "passive"))
    )
    (net (code "5") (name "/RXRF1_LAB_N") (class "Default")
      (node (ref "IC1") (pin "AM12") (pinfunction "rfgn_l_RFE_1_AM12") (pintype "passive"))
      (node (ref "MN35") (pin "1") (pinfunction "1_1") (pintype "passive"))
      (node (ref "MN37") (pin "2") (pinfunction "2_2") (pintype "passive"))
    )
    (net (code "6") (name "/RXRF1_LAB_P") (class "Default")
      (node (ref "IC1") (pin "AN11") (pinfunction "rfgp_l_RFE_1_AN11") (pintype "passive"))
      (node (ref "MN33") (pin "2") (pinfunction "2_2") (pintype "passive"))
      (node (ref "MN35") (pin "2") (pinfunction "2_2") (pintype "passive"))
    )
    (net (code "7") (name "/RXRF1_LBB_N") (class "Default")
      (node (ref "MN34") (pin "1") (pinfunction "1_1") (pintype "passive"))
      (node (ref "MN37") (pin "1") (pinfunction "1_1") (pintype "passive"))
      (node (ref "T5") (pin "3") (pinfunction "3_3") (pintype "passive"))
    )
    (net (code "8") (name "/RXRF1_LBB_P") (class "Default")
      (node (ref "MN33") (pin "1") (pinfunction "1_1") (pintype "passive"))
      (node (ref "MN34") (pin "2") (pinfunction "2_2") (pintype "passive"))
      (node (ref "T5") (pin "1") (pinfunction "1_1") (pintype "passive"))
    )
    (net (code "9") (name "/RXRF1_WAB_N") (class "Default")
      (node (ref "IC1") (pin "AP10") (pinfunction "rfgn_w_RFE_1_AP10") (pintype "passive"))
      (node (ref "MN51") (pin "2") (pinfunction "2_2") (pintype "passive"))
      (node (ref "MN53") (pin "2") (pinfunction "2_2") (pintype "passive"))
    )
    (net (code "10") (name "/RXRF1_WAB_P") (class "Default")
      (node (ref "IC1") (pin "AN9") (pinfunction "rfgp_w_RFE_1_AN9") (pintype "passive"))
      (node (ref "MN49") (pin "2") (pinfunction "2_2") (pintype "passive"))
      (node (ref "MN51") (pin "1") (pinfunction "1_1") (pintype "passive"))
    )
    (net (code "11") (name "/RXRF1_WBB_N") (class "Default")
      (node (ref "MN50") (pin "1") (pinfunction "1_1") (pintype "passive"))
      (node (ref "MN53") (pin "1") (pinfunction "1_1") (pintype "passive"))
      (node (ref "T9") (pin "3") (pinfunction "3_3") (pintype "passive"))
    )
    (net (code "12") (name "/RXRF1_WBB_P") (class "Default")
      (node (ref "MN49") (pin "1") (pinfunction "1_1") (pintype "passive"))
      (node (ref "MN50") (pin "2") (pinfunction "2_2") (pintype "passive"))
      (node (ref "T9") (pin "1") (pinfunction "1_1") (pintype "passive"))
    )
    (net (code "13") (name "/RXRF2_HAB_N") (class "Default")
      (node (ref "IC1") (pin "AM8") (pinfunction "rfgn_h_RFE_2_AM8") (pintype "passive"))
      (node (ref "MN47") (pin "1") (pinfunction "1_1") (pintype "passive"))
      (node (ref "MN48") (pin "2") (pinfunction "2_2") (pintype "passive"))
    )
    (net (code "14") (name "/RXRF2_HAB_P") (class "Default")
      (node (ref "IC1") (pin "AN7") (pinfunction "rfgp_h_RFE_2_AN7") (pintype "passive"))
      (node (ref "MN44") (pin "2") (pinfunction "2_2") (pintype "passive"))
      (node (ref "MN47") (pin "2") (pinfunction "2_2") (pintype "passive"))
    )
    (net (code "15") (name "/RXRF2_HBB_N") (class "Default")
      (node (ref "MN46") (pin "1") (pinfunction "1_1") (pintype "passive"))
      (node (ref "MN48") (pin "1") (pinfunction "1_1") (pintype "passive"))
      (node (ref "T8") (pin "6") (pinfunction "6_6") (pintype "passive"))
    )
    (net (code "16") (name "/RXRF2_HBB_P") (class "Default")
      (node (ref "MN44") (pin "1") (pinfunction "1_1") (pintype "passive"))
      (node (ref "MN46") (pin "2") (pinfunction "2_2") (pintype "passive"))
      (node (ref "T8") (pin "4") (pinfunction "4_4") (pintype "passive"))
    )
    (net (code "17") (name "/RXRF2_LAB_N") (class "Default")
      (node (ref "IC1") (pin "AP6") (pinfunction "rfgn_l_RFE_2_AP6") (pintype "passive"))
      (node (ref "MN39") (pin "1") (pinfunction "1_1") (pintype "passive"))
      (node (ref "MN40") (pin "2") (pinfunction "2_2") (pintype "passive"))
    )
    (net (code "18") (name "/RXRF2_LAB_P") (class "Default")
      (node (ref "IC1") (pin "AN5") (pinfunction "rfgp_l_RFE_2_AN5") (pintype "passive"))
      (node (ref "MN36") (pin "2") (pinfunction "2_2") (pintype "passive"))
      (node (ref "MN39") (pin "2") (pinfunction "2_2") (pintype "passive"))
    )
    (net (code "19") (name "/RXRF2_LBB_N") (class "Default")
      (node (ref "MN38") (pin "1") (pinfunction "1_1") (pintype "passive"))
      (node (ref "MN40") (pin "1") (pinfunction "1_1") (pintype "passive"))
      (node (ref "T6") (pin "3") (pinfunction "3_3") (pintype "passive"))
    )
    (net (code "20") (name "/RXRF2_LBB_P") (class "Default")
      (node (ref "MN36") (pin "1") (pinfunction "1_1") (pintype "passive"))
      (node (ref "MN38") (pin "2") (pinfunction "2_2") (pintype "passive"))
      (node (ref "T6") (pin "1") (pinfunction "1_1") (pintype "passive"))
    )
    (net (code "21") (name "/RXRF2_WAB_N") (class "Default")
      (node (ref "IC1") (pin "AM4") (pinfunction "rfgn_w_RFE_2_AM4") (pintype "passive"))
      (node (ref "MN55") (pin "2") (pinfunction "2_2") (pintype "passive"))
      (node (ref "MN56") (pin "2") (pinfunction "2_2") (pintype "passive"))
    )
    (net (code "22") (name "/RXRF2_WAB_P") (class "Default")
      (node (ref "IC1") (pin "AN3") (pinfunction "rfgp_w_RFE_2_AN3") (pintype "passive"))
      (node (ref "MN52") (pin "2") (pinfunction "2_2") (pintype "passive"))
      (node (ref "MN55") (pin "1") (pinfunction "1_1") (pintype "passive"))
    )
    (net (code "23") (name "/RXRF2_WBB_N") (class "Default")
      (node (ref "MN54") (pin "1") (pinfunction "1_1") (pintype "passive"))
      (node (ref "MN56") (pin "1") (pinfunction "1_1") (pintype "passive"))
      (node (ref "T10") (pin "1") (pinfunction "1_1") (pintype "passive"))
    )
    (net (code "24") (name "/RXRF2_WBB_P") (class "Default")
      (node (ref "MN52") (pin "1") (pinfunction "1_1") (pintype "passive"))
      (node (ref "MN54") (pin "2") (pinfunction "2_2") (pintype "passive"))
      (node (ref "T10") (pin "3") (pinfunction "3_3") (pintype "passive"))
    )
    (net (code "25") (name "/TXRF1_1AB_N") (class "Default")
      (node (ref "IC1") (pin "A7") (pinfunction "pa1on_1_A7") (pintype "passive"))
      (node (ref "MN10") (pin "1") (pinfunction "1_1") (pintype "passive"))
      (node (ref "MN12") (pin "1") (pinfunction "1_1") (pintype "passive"))
      (node (ref "MN5") (pin "1") (pinfunction "1_1") (pintype "passive"))
    )
    (net (code "26") (name "/TXRF1_1AB_P") (class "Default")
      (node (ref "IC1") (pin "B8") (pinfunction "pa1op_1_B8") (pintype "passive"))
      (node (ref "MN10") (pin "2") (pinfunction "2_2") (pintype "passive"))
      (node (ref "MN6") (pin "1") (pinfunction "1_1") (pintype "passive"))
      (node (ref "MN9") (pin "2") (pinfunction "2_2") (pintype "passive"))
    )
    (net (code "27") (name "/TXRF1_1BB_N") (class "Default")
      (node (ref "MN11") (pin "1") (pinfunction "1_1") (pintype "passive"))
      (node (ref "T1") (pin "3") (pinfunction "3_3") (pintype "passive"))
    )
    (net (code "28") (name "/TXRF1_1BB_P") (class "Default")
      (node (ref "MN11") (pin "2") (pinfunction "2_2") (pintype "passive"))
      (node (ref "MN9") (pin "1") (pinfunction "1_1") (pintype "passive"))
      (node (ref "T1") (pin "1") (pinfunction "1_1") (pintype "passive"))
    )
    (net (code "29") (name "/TXRF1_2AB_N") (class "Default")
      (node (ref "IC1") (pin "B10") (pinfunction "pa2on_1_B10") (pintype "passive"))
      (node (ref "MN21") (pin "1") (pinfunction "1_1") (pintype "passive"))
      (node (ref "MN26") (pin "2") (pinfunction "2_2") (pintype "passive"))
      (node (ref "MN28") (pin "2") (pinfunction "2_2") (pintype "passive"))
    )
    (net (code "30") (name "/TXRF1_2AB_P") (class "Default")
      (node (ref "IC1") (pin "A9") (pinfunction "pa2op_1_A9") (pintype "passive"))
      (node (ref "MN22") (pin "1") (pinfunction "1_1") (pintype "passive"))
      (node (ref "MN23") (pin "2") (pinfunction "2_2") (pintype "passive"))
      (node (ref "MN26") (pin "1") (pinfunction "1_1") (pintype "passive"))
    )
    (net (code "31") (name "/TXRF1_2BB_N") (class "Default")
      (node (ref "MN27") (pin "1") (pinfunction "1_1") (pintype "passive"))
      (node (ref "MN28") (pin "1") (pinfunction "1_1") (pintype "passive"))
      (node (ref "T3") (pin "4") (pinfunction "4_4") (pintype "passive"))
    )
    (net (code "32") (name "/TXRF1_2BB_P") (class "Default")
      (node (ref "MN23") (pin "1") (pinfunction "1_1") (pintype "passive"))
      (node (ref "MN27") (pin "2") (pinfunction "2_2") (pintype "passive"))
      (node (ref "T3") (pin "6") (pinfunction "6_6") (pintype "passive"))
    )
    (net (code "33") (name "/TXRF2_1AB_N") (class "Default")
      (node (ref "IC1") (pin "C11") (pinfunction "pa1on_2_C11") (pintype "passive"))
      (node (ref "MN14") (pin "1") (pinfunction "1_1") (pintype "passive"))
      (node (ref "MN16") (pin "1") (pinfunction "1_1") (pintype "passive"))
      (node (ref "MN7") (pin "1") (pinfunction "1_1") (pintype "passive"))
    )
    (net (code "34") (name "/TXRF2_1AB_P") (class "Default")
      (node (ref "IC1") (pin "B12") (pinfunction "pa1op_2_B12") (pintype "passive"))
      (node (ref "MN13") (pin "2") (pinfunction "2_2") (pintype "passive"))
      (node (ref "MN14") (pin "2") (pinfunction "2_2") (pintype "passive"))
      (node (ref "MN8") (pin "1") (pinfunction "1_1") (pintype "passive"))
    )
    (net (code "35") (name "/TXRF2_1BB_N") (class "Default")
      (node (ref "MN15") (pin "1") (pinfunction "1_1") (pintype "passive"))
      (node (ref "MN16") (pin "2") (pinfunction "2_2") (pintype "passive"))
      (node (ref "T2") (pin "3") (pinfunction "3_3") (pintype "passive"))
    )
    (net (code "36") (name "/TXRF2_1BB_P") (class "Default")
      (node (ref "MN13") (pin "1") (pinfunction "1_1") (pintype "passive"))
      (node (ref "MN15") (pin "2") (pinfunction "2_2") (pintype "passive"))
      (node (ref "T2") (pin "1") (pinfunction "1_1") (pintype "passive"))
    )
    (net (code "37") (name "/TXRF2_2AB_N") (class "Default")
      (node (ref "IC1") (pin "B14") (pinfunction "pa2on_2_B14") (pintype "passive"))
      (node (ref "MN24") (pin "1") (pinfunction "1_1") (pintype "passive"))
      (node (ref "MN30") (pin "2") (pinfunction "2_2") (pintype "passive"))
      (node (ref "MN32") (pin "2") (pinfunction "2_2") (pintype "passive"))
    )
    (net (code "38") (name "/TXRF2_2AB_P") (class "Default")
      (node (ref "IC1") (pin "A13") (pinfunction "pa2op_2_A13") (pintype "passive"))
      (node (ref "MN25") (pin "1") (pinfunction "1_1") (pintype "passive"))
      (node (ref "MN29") (pin "2") (pinfunction "2_2") (pintype "passive"))
      (node (ref "MN30") (pin "1") (pinfunction "1_1") (pintype "passive"))
    )
    (net (code "39") (name "/TXRF2_2BB_N") (class "Default")
      (node (ref "MN31") (pin "1") (pinfunction "1_1") (pintype "passive"))
      (node (ref "MN32") (pin "1") (pinfunction "1_1") (pintype "passive"))
      (node (ref "T4") (pin "4") (pinfunction "4_4") (pintype "passive"))
    )
    (net (code "40") (name "/TXRF2_2BB_P") (class "Default")
      (node (ref "MN29") (pin "1") (pinfunction "1_1") (pintype "passive"))
      (node (ref "MN31") (pin "2") (pinfunction "2_2") (pintype "passive"))
      (node (ref "T4") (pin "6") (pinfunction "6_6") (pintype "passive"))
    )
    (net (code "41") (name "GND") (class "Default")
      (node (ref "C10") (pin "1") (pinfunction "1_1") (pintype "passive"))
      (node (ref "C11") (pin "1") (pinfunction "1_1") (pintype "passive"))
      (node (ref "C12") (pin "1") (pinfunction "1_1") (pintype "passive"))
      (node (ref "C13") (pin "1") (pinfunction "1_1") (pintype "passive"))
      (node (ref "C4") (pin "1") (pinfunction "1_1") (pintype "passive"))
      (node (ref "C5") (pin "1") (pinfunction "1_1") (pintype "passive"))
      (node (ref "C6") (pin "1") (pinfunction "1_1") (pintype "passive"))
      (node (ref "C7") (pin "1") (pinfunction "1_1") (pintype "passive"))
      (node (ref "IC1") (pin "AJ7") (pinfunction "rfsn_l_RFE_2_AJ7") (pintype "passive"))
      (node (ref "IC1") (pin "AJ9") (pinfunction "rfsp_l_RFE_2_AJ9") (pintype "passive"))
      (node (ref "IC1") (pin "AK12") (pinfunction "rfsn_l_RFE_1_AK12") (pintype "passive"))
      (node (ref "IC1") (pin "AL13") (pinfunction "rfsp_l_RFE_1_AL13") (pintype "passive"))
      (node (ref "J1") (pin "2") (pinfunction "Y_2") (pintype "passive"))
      (node (ref "J10") (pin "2") (pinfunction "Y_2") (pintype "passive"))
      (node (ref "J2") (pin "2") (pinfunction "Y_2") (pintype "passive"))
      (node (ref "J3") (pin "2") (pinfunction "Y_2") (pintype "passive"))
      (node (ref "J4") (pin "2") (pinfunction "Y_2") (pintype "passive"))
      (node (ref "J5") (pin "2") (pinfunction "Y_2") (pintype "passive"))
      (node (ref "J6") (pin "2") (pinfunction "Y_2") (pintype "passive"))
      (node (ref "J7") (pin "2") (pinfunction "Y_2") (pintype "passive"))
      (node (ref "J8") (pin "2") (pinfunction "Y_2") (pintype "passive"))
      (node (ref "J9") (pin "2") (pinfunction "Y_2") (pintype "passive"))
      (node (ref "T1") (pin "2") (pinfunction "2_2") (pintype "passive"))
      (node (ref "T1") (pin "6") (pinfunction "6_6") (pintype "passive"))
      (node (ref "T10") (pin "2") (pinfunction "2_2") (pintype "passive"))
      (node (ref "T10") (pin "4") (pinfunction "4_4") (pintype "passive"))
      (node (ref "T2") (pin "2") (pinfunction "2_2") (pintype "passive"))
      (node (ref "T2") (pin "6") (pinfunction "6_6") (pintype "passive"))
      (node (ref "T3") (pin "3") (pinfunction "3_3") (pintype "passive"))
      (node (ref "T4") (pin "3") (pinfunction "3_3") (pintype "passive"))
      (node (ref "T5") (pin "2") (pinfunction "2_2") (pintype "passive"))
      (node (ref "T5") (pin "4") (pinfunction "4_4") (pintype "passive"))
      (node (ref "T6") (pin "2") (pinfunction "2_2") (pintype "passive"))
      (node (ref "T6") (pin "4") (pinfunction "4_4") (pintype "passive"))
      (node (ref "T7") (pin "2") (pinfunction "2_2") (pintype "passive"))
      (node (ref "T8") (pin "2") (pinfunction "2_2") (pintype "passive"))
      (node (ref "T9") (pin "2") (pinfunction "2_2") (pintype "passive"))
      (node (ref "T9") (pin "4") (pinfunction "4_4") (pintype "passive"))
    )
    (net (code "42") (name "Net-(C8-Pad2)") (class "Default")
      (node (ref "C8") (pin "2") (pinfunction "2_2") (pintype "passive"))
      (node (ref "T1") (pin "4") (pinfunction "4_4") (pintype "passive"))
    )
    (net (code "43") (name "Net-(C9-Pad2)") (class "Default")
      (node (ref "C9") (pin "2") (pinfunction "2_2") (pintype "passive"))
      (node (ref "T2") (pin "4") (pinfunction "4_4") (pintype "passive"))
    )
    (net (code "44") (name "Net-(C14-Pad2)") (class "Default")
      (node (ref "C14") (pin "2") (pinfunction "2_2") (pintype "passive"))
      (node (ref "T3") (pin "2") (pinfunction "2_2") (pintype "passive"))
    )
    (net (code "45") (name "Net-(C15-Pad2)") (class "Default")
      (node (ref "C15") (pin "2") (pinfunction "2_2") (pintype "passive"))
      (node (ref "T4") (pin "2") (pinfunction "2_2") (pintype "passive"))
    )
    (net (code "46") (name "Net-(C16-Pad2)") (class "Default")
      (node (ref "C16") (pin "2") (pinfunction "2_2") (pintype "passive"))
      (node (ref "T5") (pin "6") (pinfunction "6_6") (pintype "passive"))
    )
    (net (code "47") (name "Net-(C17-Pad2)") (class "Default")
      (node (ref "C17") (pin "2") (pinfunction "2_2") (pintype "passive"))
      (node (ref "T6") (pin "6") (pinfunction "6_6") (pintype "passive"))
    )
    (net (code "48") (name "Net-(C18-Pad2)") (class "Default")
      (node (ref "C18") (pin "2") (pinfunction "2_2") (pintype "passive"))
      (node (ref "T7") (pin "3") (pinfunction "3_3") (pintype "passive"))
    )
    (net (code "49") (name "Net-(C19-Pad2)") (class "Default")
      (node (ref "C19") (pin "2") (pinfunction "2_2") (pintype "passive"))
      (node (ref "T8") (pin "3") (pinfunction "3_3") (pintype "passive"))
    )
    (net (code "50") (name "Net-(C20-Pad2)") (class "Default")
      (node (ref "C20") (pin "2") (pinfunction "2_2") (pintype "passive"))
      (node (ref "T9") (pin "6") (pinfunction "6_6") (pintype "passive"))
    )
    (net (code "51") (name "Net-(C21-Pad2)") (class "Default")
      (node (ref "C21") (pin "2") (pinfunction "2_2") (pintype "passive"))
      (node (ref "T10") (pin "6") (pinfunction "6_6") (pintype "passive"))
    )
    (net (code "52") (name "Net-(J1-X)") (class "Default")
      (node (ref "C8") (pin "1") (pinfunction "1_1") (pintype "passive"))
      (node (ref "J1") (pin "1") (pinfunction "X_1") (pintype "passive"))
    )
    (net (code "53") (name "Net-(J2-X)") (class "Default")
      (node (ref "C9") (pin "1") (pinfunction "1_1") (pintype "passive"))
      (node (ref "J2") (pin "1") (pinfunction "X_1") (pintype "passive"))
    )
    (net (code "54") (name "Net-(J3-X)") (class "Default")
      (node (ref "C14") (pin "1") (pinfunction "1_1") (pintype "passive"))
      (node (ref "J3") (pin "1") (pinfunction "X_1") (pintype "passive"))
    )
    (net (code "55") (name "Net-(J4-X)") (class "Default")
      (node (ref "C15") (pin "1") (pinfunction "1_1") (pintype "passive"))
      (node (ref "J4") (pin "1") (pinfunction "X_1") (pintype "passive"))
    )
    (net (code "56") (name "Net-(J5-X)") (class "Default")
      (node (ref "C16") (pin "1") (pinfunction "1_1") (pintype "passive"))
      (node (ref "J5") (pin "1") (pinfunction "X_1") (pintype "passive"))
    )
    (net (code "57") (name "Net-(J6-X)") (class "Default")
      (node (ref "C17") (pin "1") (pinfunction "1_1") (pintype "passive"))
      (node (ref "J6") (pin "1") (pinfunction "X_1") (pintype "passive"))
    )
    (net (code "58") (name "Net-(J7-X)") (class "Default")
      (node (ref "C18") (pin "1") (pinfunction "1_1") (pintype "passive"))
      (node (ref "J7") (pin "1") (pinfunction "X_1") (pintype "passive"))
    )
    (net (code "59") (name "Net-(J8-X)") (class "Default")
      (node (ref "C19") (pin "1") (pinfunction "1_1") (pintype "passive"))
      (node (ref "J8") (pin "1") (pinfunction "X_1") (pintype "passive"))
    )
    (net (code "60") (name "Net-(J9-X)") (class "Default")
      (node (ref "C20") (pin "1") (pinfunction "1_1") (pintype "passive"))
      (node (ref "J9") (pin "1") (pinfunction "X_1") (pintype "passive"))
    )
    (net (code "61") (name "Net-(J10-X)") (class "Default")
      (node (ref "C21") (pin "1") (pinfunction "1_1") (pintype "passive"))
      (node (ref "J10") (pin "1") (pinfunction "X_1") (pintype "passive"))
    )
    (net (code "62") (name "Net-(MN1-Pad1)") (class "Default")
      (node (ref "MN1") (pin "1") (pinfunction "1_1") (pintype "passive"))
      (node (ref "MN5") (pin "2") (pinfunction "2_2") (pintype "passive"))
    )
    (net (code "63") (name "Net-(MN2-Pad1)") (class "Default")
      (node (ref "MN2") (pin "1") (pinfunction "1_1") (pintype "passive"))
      (node (ref "MN6") (pin "2") (pinfunction "2_2") (pintype "passive"))
    )
    (net (code "64") (name "Net-(MN3-Pad1)") (class "Default")
      (node (ref "MN3") (pin "1") (pinfunction "1_1") (pintype "passive"))
      (node (ref "MN7") (pin "2") (pinfunction "2_2") (pintype "passive"))
    )
    (net (code "65") (name "Net-(MN4-Pad1)") (class "Default")
      (node (ref "MN4") (pin "1") (pinfunction "1_1") (pintype "passive"))
      (node (ref "MN8") (pin "2") (pinfunction "2_2") (pintype "passive"))
    )
    (net (code "66") (name "Net-(MN17-Pad1)") (class "Default")
      (node (ref "MN17") (pin "1") (pinfunction "1_1") (pintype "passive"))
      (node (ref "MN21") (pin "2") (pinfunction "2_2") (pintype "passive"))
    )
    (net (code "67") (name "Net-(MN18-Pad1)") (class "Default")
      (node (ref "MN18") (pin "1") (pinfunction "1_1") (pintype "passive"))
      (node (ref "MN22") (pin "2") (pinfunction "2_2") (pintype "passive"))
    )
    (net (code "68") (name "Net-(MN19-Pad1)") (class "Default")
      (node (ref "MN19") (pin "1") (pinfunction "1_1") (pintype "passive"))
      (node (ref "MN24") (pin "2") (pinfunction "2_2") (pintype "passive"))
    )
    (net (code "69") (name "Net-(MN20-Pad1)") (class "Default")
      (node (ref "MN20") (pin "1") (pinfunction "1_1") (pintype "passive"))
      (node (ref "MN25") (pin "2") (pinfunction "2_2") (pintype "passive"))
    )
    (net (code "70") (name "VCC1P8_LMS") (class "Default")
      (node (ref "C10") (pin "2") (pinfunction "2_2") (pintype "passive"))
      (node (ref "C11") (pin "2") (pinfunction "2_2") (pintype "passive"))
      (node (ref "C12") (pin "2") (pinfunction "2_2") (pintype "passive"))
      (node (ref "C13") (pin "2") (pinfunction "2_2") (pintype "passive"))
      (node (ref "C4") (pin "2") (pinfunction "2_2") (pintype "passive"))
      (node (ref "C5") (pin "2") (pinfunction "2_2") (pintype "passive"))
      (node (ref "C6") (pin "2") (pinfunction "2_2") (pintype "passive"))
      (node (ref "C7") (pin "2") (pinfunction "2_2") (pintype "passive"))
      (node (ref "MN1") (pin "2") (pinfunction "2_2") (pintype "passive"))
      (node (ref "MN17") (pin "2") (pinfunction "2_2") (pintype "passive"))
      (node (ref "MN18") (pin "2") (pinfunction "2_2") (pintype "passive"))
      (node (ref "MN19") (pin "2") (pinfunction "2_2") (pintype "passive"))
      (node (ref "MN2") (pin "2") (pinfunction "2_2") (pintype "passive"))
      (node (ref "MN20") (pin "2") (pinfunction "2_2") (pintype "passive"))
      (node (ref "MN3") (pin "2") (pinfunction "2_2") (pintype "passive"))
      (node (ref "MN4") (pin "2") (pinfunction "2_2") (pintype "passive"))
    )
    (net (code "71") (name "unconnected-(MN12-Pad2)") (class "Default")
      (node (ref "MN12") (pin "2") (pinfunction "2_2") (pintype "passive"))
    )
  )
)
